# Sheet1.net
KiCad netlist of a schematic drawn in Altium Designer
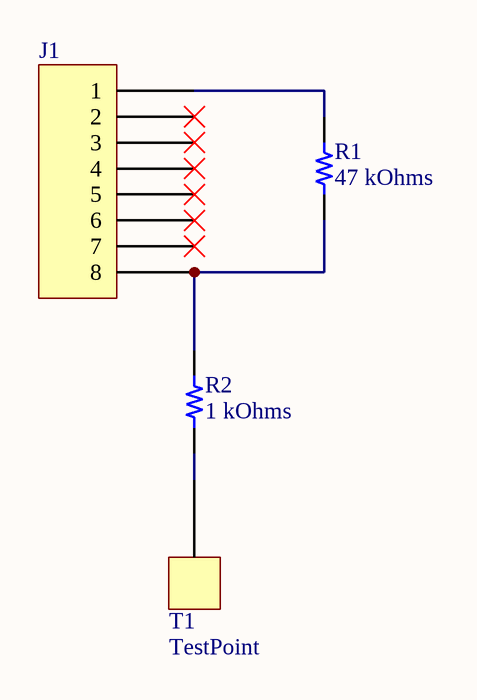
[diagram p0: Sheet1.SchDoc]

(export (version "E")
  (design (tool "Eeschema 10.0.6"))
  (components
    (comp (ref "J1")
      (value "0022272081")
      (footprint "MOLEX KK 0022272081")
      (description "CONN HEADER VERT 8POS 2.54MM")
      (fields (field (name "MANUFACTURER") "Molex"))
      (libsource (lib "Celestial Altium Library - altium_library") (part "8 Pin"))
    )
    (comp (ref "R1")
      (value "47 kOhms")
      (footprint "RES 0805_2012")
      (description "RES SMD 47K OHM 0.5% 1/8W 0805")
      (fields (field (name "PART NUMBER") "RT0805DRE0747KL") (field (name "MANUFACTURER") "Yageo"))
      (libsource (lib "Celestial Altium Library - altium_library") (part "Resistor"))
    )
    (comp (ref "R2")
      (value "1 kOhms")
      (footprint "RES 0805_2012")
      (description "RES SMD 1K OHM 0.1% 1/10W 0805")
      (fields
        (field (name "PART NUMBER") "CPF0805B1K0E")
        (field (name "MANUFACTURER") "TE Connectivity Passive Product")
      )
      (libsource (lib "Celestial Altium Library - altium_library") (part "Resistor"))
    )
    (comp (ref "T1")
      (value "TestPoint")
      (footprint "TestPoint")
      (libsource (lib "Schlib1") (part "TestPoint"))
    )
  )
  (nets
    (net (code "1") (name "Net-(J1-Pad1)") (class "Default")
      (node (ref "J1") (pin "1") (pinfunction "1_1") (pintype "passive"))
      (node (ref "R1") (pin "2") (pinfunction "2_2") (pintype "passive"))
    )
    (net (code "2") (name "Net-(J1-Pad8)") (class "Default")
      (node (ref "J1") (pin "8") (pinfunction "8_8") (pintype "passive"))
      (node (ref "R1") (pin "1") (pinfunction "1_1") (pintype "passive"))
      (node (ref "R2") (pin "2") (pinfunction "2_2") (pintype "passive"))
    )
    (net (code "3") (name "Net-(R2-Pad1)") (class "Default")
      (node (ref "R2") (pin "1") (pinfunction "1_1") (pintype "passive"))
      (node (ref "T1") (pin "1") (pinfunction "1_1") (pintype "passive"))
    )
    (net (code "4") (name "unconnected-(J1-Pad2)") (class "Default")
      (node (ref "J1") (pin "2") (pinfunction "2_2") (pintype "passive+no_connect"))
    )
    (net (code "5") (name "unconnected-(J1-Pad3)") (class "Default")
      (node (ref "J1") (pin "3") (pinfunction "3_3") (pintype "passive+no_connect"))
    )
    (net (code "6") (name "unconnected-(J1-Pad4)") (class "Default")
      (node (ref "J1") (pin "4") (pinfunction "4_4") (pintype "passive+no_connect"))
    )
    (net (code "7") (name "unconnected-(J1-Pad5)") (class "Default")
      (node (ref "J1") (pin "5") (pinfunction "5_5") (pintype "passive+no_connect"))
    )
    (net (code "8") (name "unconnected-(J1-Pad6)") (class "Default")
      (node (ref "J1") (pin "6") (pinfunction "6_6") (pintype "passive+no_connect"))
    )
    (net (code "9") (name "unconnected-(J1-Pad7)") (class "Default")
      (node (ref "J1") (pin "7") (pinfunction "7_7") (pintype "passive+no_connect"))
    )
  )
)
